# FlowKnow.net
KiCad netlist of a schematic drawn in EAGLE
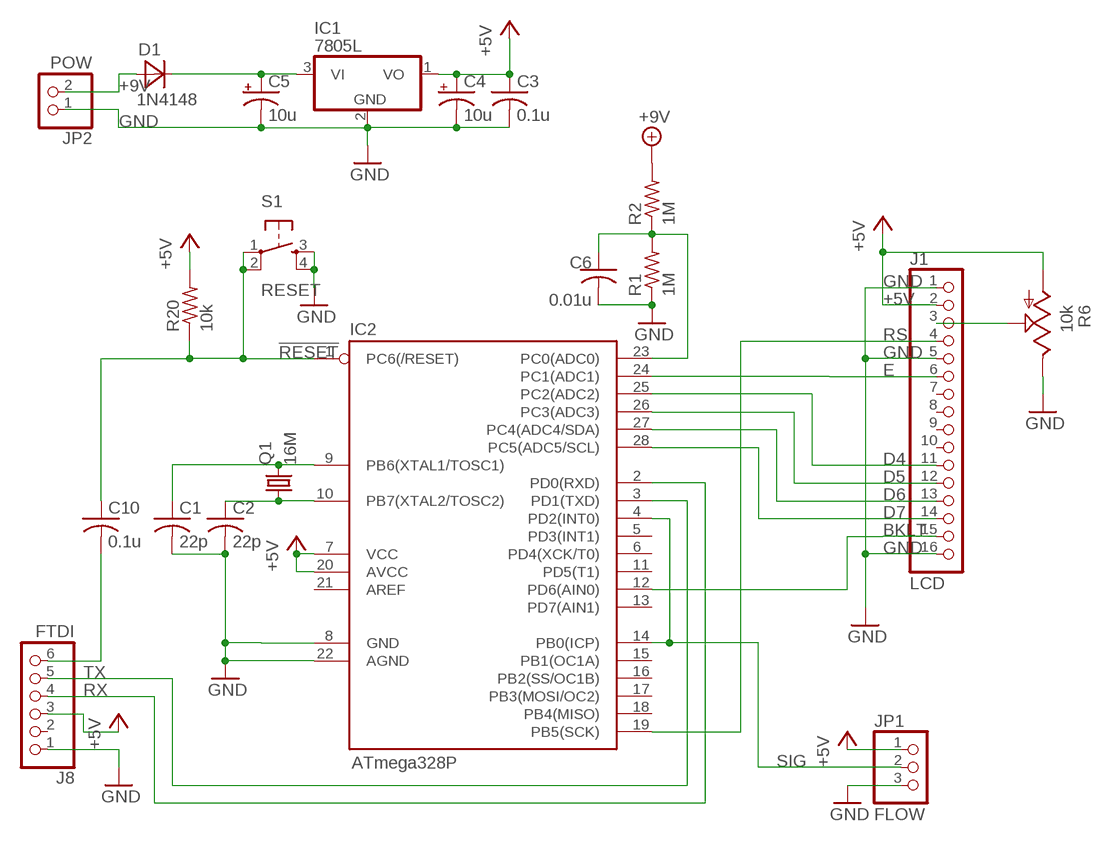
[diagram p0: schematic, sheet 1]

(export (version "E")
  (design (tool "Eeschema 10.0.6"))
  (components
    (comp (ref "C1")
      (value "22p")
      (footprint "eagle-import:C025-025X050")
      (libsource (lib "eagle-import") (part "C-US025-025X050"))
    )
    (comp (ref "C2")
      (value "22p")
      (footprint "eagle-import:C025-025X050")
      (libsource (lib "eagle-import") (part "C-US025-025X050"))
    )
    (comp (ref "C3")
      (value "0.1u")
      (footprint "eagle-import:C025-025X050")
      (libsource (lib "eagle-import") (part "C-US025-025X050"))
    )
    (comp (ref "C4")
      (value "10u")
      (footprint "eagle-import:E2-4")
      (libsource (lib "eagle-import") (part "CPOL-USE2-4"))
    )
    (comp (ref "C5")
      (value "10u")
      (footprint "eagle-import:E2,5-5")
      (libsource (lib "eagle-import") (part "CPOL-USE2.5-5"))
    )
    (comp (ref "C6")
      (value "0.01u")
      (footprint "eagle-import:C025-025X050")
      (libsource (lib "eagle-import") (part "C-US025-025X050"))
    )
    (comp (ref "C10")
      (value "0.1u")
      (footprint "eagle-import:C025-025X050")
      (libsource (lib "eagle-import") (part "C-US025-025X050"))
    )
    (comp (ref "D1")
      (value "1N4148")
      (footprint "eagle-import:DO35-5")
      (libsource (lib "eagle-import") (part "DIODE-DO35-5"))
    )
    (comp (ref "IC1")
      (value "7805L")
      (footprint "eagle-import:TO92")
      (libsource (lib "eagle-import") (part "78L05"))
    )
    (comp (ref "IC2")
      (value "ATmega328P")
      (footprint "eagle-import:DIL28-3")
      (libsource (lib "eagle-import") (part "AVR-MEGA8-PPTH"))
    )
    (comp (ref "J1")
      (value "LCD")
      (footprint "eagle-import:1X16")
      (libsource (lib "eagle-import") (part "PINHD-1X16"))
    )
    (comp (ref "J8")
      (value "FTDI")
      (footprint "eagle-import:1X06_90")
      (libsource (lib "eagle-import") (part "PINHD-1X6/90"))
    )
    (comp (ref "JP1")
      (value "FLOW")
      (footprint "eagle-import:1X03_90")
      (libsource (lib "eagle-import") (part "PINHD-1X3/90"))
    )
    (comp (ref "JP2")
      (value "POW")
      (footprint "eagle-import:1X02")
      (libsource (lib "eagle-import") (part "PINHD-1X2"))
    )
    (comp (ref "Q1")
      (value "16M")
      (footprint "eagle-import:HC49_S")
      (libsource (lib "eagle-import") (part "CRYSTALHC49S"))
    )
    (comp (ref "R1")
      (value "1M")
      (footprint "eagle-import:0204_7")
      (libsource (lib "eagle-import") (part "R-US_0204/7"))
    )
    (comp (ref "R2")
      (value "1M")
      (footprint "eagle-import:0204_7")
      (libsource (lib "eagle-import") (part "R-US_0204/7"))
    )
    (comp (ref "R6")
      (value "10k")
      (footprint "eagle-import:CT6")
      (libsource (lib "eagle-import") (part "TRIM_US-CT6"))
    )
    (comp (ref "R20")
      (value "10k")
      (footprint "eagle-import:0204_7")
      (libsource (lib "eagle-import") (part "R-US_0204/7"))
    )
    (comp (ref "S1")
      (value "RESET")
      (footprint "eagle-import:TACTILE-PTH")
      (libsource (lib "eagle-import") (part "TAC_SWITCHPTH"))
    )
  )
  (nets
    (net (code "1") (name "+5V") (class "Default")
      (node (ref "C3") (pin "1") (pinfunction "1_1") (pintype "passive"))
      (node (ref "C4") (pin "+") (pinfunction "+_+") (pintype "passive"))
      (node (ref "IC1") (pin "1") (pinfunction "VO_1") (pintype "passive"))
      (node (ref "IC2") (pin "20") (pinfunction "AVCC_20") (pintype "bidirectional"))
      (node (ref "IC2") (pin "7") (pinfunction "VCC_7") (pintype "bidirectional"))
      (node (ref "J1") (pin "2") (pinfunction "2_2") (pintype "passive"))
      (node (ref "J8") (pin "3") (pinfunction "3_3") (pintype "passive"))
      (node (ref "JP1") (pin "1") (pinfunction "1_1") (pintype "passive"))
      (node (ref "R20") (pin "2") (pinfunction "2_2") (pintype "passive"))
      (node (ref "R6") (pin "A") (pinfunction "A_A") (pintype "passive"))
    )
    (net (code "2") (name "+9V") (class "Default")
      (node (ref "D1") (pin "A") (pinfunction "A_A") (pintype "passive"))
      (node (ref "JP2") (pin "2") (pinfunction "2_2") (pintype "passive"))
      (node (ref "R2") (pin "2") (pinfunction "2_2") (pintype "passive"))
    )
    (net (code "3") (name "/BKLT") (class "Default")
      (node (ref "IC2") (pin "12") (pinfunction "PD6(AIN0)_12") (pintype "bidirectional"))
      (node (ref "J1") (pin "15") (pinfunction "15_15") (pintype "passive"))
    )
    (net (code "4") (name "/D4") (class "Default")
      (node (ref "IC2") (pin "25") (pinfunction "PC2(ADC2)_25") (pintype "bidirectional"))
      (node (ref "J1") (pin "11") (pinfunction "11_11") (pintype "passive"))
    )
    (net (code "5") (name "/D5") (class "Default")
      (node (ref "IC2") (pin "26") (pinfunction "PC3(ADC3)_26") (pintype "bidirectional"))
      (node (ref "J1") (pin "12") (pinfunction "12_12") (pintype "passive"))
    )
    (net (code "6") (name "/D6") (class "Default")
      (node (ref "IC2") (pin "27") (pinfunction "PC4(ADC4/SDA)_27") (pintype "bidirectional"))
      (node (ref "J1") (pin "13") (pinfunction "13_13") (pintype "passive"))
    )
    (net (code "7") (name "/D7") (class "Default")
      (node (ref "IC2") (pin "28") (pinfunction "PC5(ADC5/SCL)_28") (pintype "bidirectional"))
      (node (ref "J1") (pin "14") (pinfunction "14_14") (pintype "passive"))
    )
    (net (code "8") (name "/E") (class "Default")
      (node (ref "IC2") (pin "24") (pinfunction "PC1(ADC1)_24") (pintype "bidirectional"))
      (node (ref "J1") (pin "6") (pinfunction "6_6") (pintype "passive"))
    )
    (net (code "9") (name "/RS") (class "Default")
      (node (ref "IC2") (pin "19") (pinfunction "PB5(SCK)_19") (pintype "bidirectional"))
      (node (ref "J1") (pin "4") (pinfunction "4_4") (pintype "passive"))
    )
    (net (code "10") (name "/RX") (class "Default")
      (node (ref "IC2") (pin "2") (pinfunction "PD0(RXD)_2") (pintype "bidirectional"))
      (node (ref "J8") (pin "4") (pinfunction "4_4") (pintype "passive"))
    )
    (net (code "11") (name "/SIG") (class "Default")
      (node (ref "IC2") (pin "14") (pinfunction "PB0(ICP)_14") (pintype "bidirectional"))
      (node (ref "IC2") (pin "4") (pinfunction "PD2(INT0)_4") (pintype "bidirectional"))
      (node (ref "JP1") (pin "2") (pinfunction "2_2") (pintype "passive"))
    )
    (net (code "12") (name "/TX") (class "Default")
      (node (ref "IC2") (pin "3") (pinfunction "PD1(TXD)_3") (pintype "bidirectional"))
      (node (ref "J8") (pin "5") (pinfunction "5_5") (pintype "passive"))
    )
    (net (code "13") (name "/~{RESET}") (class "Default")
      (node (ref "C10") (pin "1") (pinfunction "1_1") (pintype "passive"))
      (node (ref "IC2") (pin "1") (pinfunction "PC6(/RESET)_1") (pintype "bidirectional"))
      (node (ref "R20") (pin "1") (pinfunction "1_1") (pintype "passive"))
      (node (ref "S1") (pin "1") (pinfunction "1_1") (pintype "passive"))
      (node (ref "S1") (pin "2") (pinfunction "2_2") (pintype "passive"))
    )
    (net (code "14") (name "GND") (class "Default")
      (node (ref "C1") (pin "2") (pinfunction "2_2") (pintype "passive"))
      (node (ref "C2") (pin "2") (pinfunction "2_2") (pintype "passive"))
      (node (ref "C3") (pin "2") (pinfunction "2_2") (pintype "passive"))
      (node (ref "C4") (pin "-") (pinfunction "-_-") (pintype "passive"))
      (node (ref "C5") (pin "-") (pinfunction "-_-") (pintype "passive"))
      (node (ref "C6") (pin "2") (pinfunction "2_2") (pintype "passive"))
      (node (ref "IC1") (pin "2") (pinfunction "GND_2") (pintype "passive"))
      (node (ref "IC2") (pin "22") (pinfunction "AGND_22") (pintype "bidirectional"))
      (node (ref "IC2") (pin "8") (pinfunction "GND_8") (pintype "bidirectional"))
      (node (ref "J1") (pin "1") (pinfunction "1_1") (pintype "passive"))
      (node (ref "J1") (pin "16") (pinfunction "16_16") (pintype "passive"))
      (node (ref "J1") (pin "5") (pinfunction "5_5") (pintype "passive"))
      (node (ref "J8") (pin "1") (pinfunction "1_1") (pintype "passive"))
      (node (ref "JP1") (pin "3") (pinfunction "3_3") (pintype "passive"))
      (node (ref "JP2") (pin "1") (pinfunction "1_1") (pintype "passive"))
      (node (ref "R1") (pin "1") (pinfunction "1_1") (pintype "passive"))
      (node (ref "R6") (pin "E") (pinfunction "E_E") (pintype "passive"))
      (node (ref "S1") (pin "3") (pinfunction "3_3") (pintype "passive"))
      (node (ref "S1") (pin "4") (pinfunction "4_4") (pintype "passive"))
    )
    (net (code "15") (name "Net-(C10-Pad2)") (class "Default")
      (node (ref "C10") (pin "2") (pinfunction "2_2") (pintype "passive"))
      (node (ref "J8") (pin "6") (pinfunction "6_6") (pintype "passive"))
    )
    (net (code "16") (name "Net-(IC1-VI)") (class "Default")
      (node (ref "C5") (pin "+") (pinfunction "+_+") (pintype "passive"))
      (node (ref "D1") (pin "C") (pinfunction "C_C") (pintype "passive"))
      (node (ref "IC1") (pin "3") (pinfunction "VI_3") (pintype "input"))
    )
    (net (code "17") (name "Net-(IC2-PB6(XTAL1{slash}TOSC1))") (class "Default")
      (node (ref "C1") (pin "1") (pinfunction "1_1") (pintype "passive"))
      (node (ref "IC2") (pin "9") (pinfunction "PB6(XTAL1/TOSC1)_9") (pintype "bidirectional"))
      (node (ref "Q1") (pin "2") (pinfunction "2_2") (pintype "passive"))
    )
    (net (code "18") (name "Net-(IC2-PB7(XTAL2{slash}TOSC2))") (class "Default")
      (node (ref "C2") (pin "1") (pinfunction "1_1") (pintype "passive"))
      (node (ref "IC2") (pin "10") (pinfunction "PB7(XTAL2/TOSC2)_10") (pintype "bidirectional"))
      (node (ref "Q1") (pin "1") (pinfunction "1_1") (pintype "passive"))
    )
    (net (code "19") (name "Net-(IC2-PC0(ADC0))") (class "Default")
      (node (ref "C6") (pin "1") (pinfunction "1_1") (pintype "passive"))
      (node (ref "IC2") (pin "23") (pinfunction "PC0(ADC0)_23") (pintype "bidirectional"))
      (node (ref "R1") (pin "2") (pinfunction "2_2") (pintype "passive"))
      (node (ref "R2") (pin "1") (pinfunction "1_1") (pintype "passive"))
    )
    (net (code "20") (name "Net-(J1-Pad3)") (class "Default")
      (node (ref "J1") (pin "3") (pinfunction "3_3") (pintype "passive"))
      (node (ref "R6") (pin "S") (pinfunction "S_S") (pintype "passive"))
    )
    (net (code "21") (name "unconnected-(IC2-AREF-Pad21)") (class "Default")
      (node (ref "IC2") (pin "21") (pinfunction "AREF_21") (pintype "bidirectional"))
    )
    (net (code "22") (name "unconnected-(IC2-PB1(OC1A)-Pad15)") (class "Default")
      (node (ref "IC2") (pin "15") (pinfunction "PB1(OC1A)_15") (pintype "bidirectional"))
    )
    (net (code "23") (name "unconnected-(IC2-PB2(SS{slash}OC1B)-Pad16)") (class "Default")
      (node (ref "IC2") (pin "16") (pinfunction "PB2(SS/OC1B)_16") (pintype "bidirectional"))
    )
    (net (code "24") (name "unconnected-(IC2-PB3(MOSI{slash}OC2)-Pad17)") (class "Default")
      (node (ref "IC2") (pin "17") (pinfunction "PB3(MOSI/OC2)_17") (pintype "bidirectional"))
    )
    (net (code "25") (name "unconnected-(IC2-PB4(MISO)-Pad18)") (class "Default")
      (node (ref "IC2") (pin "18") (pinfunction "PB4(MISO)_18") (pintype "bidirectional"))
    )
    (net (code "26") (name "unconnected-(IC2-PD3(INT1)-Pad5)") (class "Default")
      (node (ref "IC2") (pin "5") (pinfunction "PD3(INT1)_5") (pintype "bidirectional"))
    )
    (net (code "27") (name "unconnected-(IC2-PD4(XCK{slash}T0)-Pad6)") (class "Default")
      (node (ref "IC2") (pin "6") (pinfunction "PD4(XCK/T0)_6") (pintype "bidirectional"))
    )
    (net (code "28") (name "unconnected-(IC2-PD5(T1)-Pad11)") (class "Default")
      (node (ref "IC2") (pin "11") (pinfunction "PD5(T1)_11") (pintype "bidirectional"))
    )
    (net (code "29") (name "unconnected-(IC2-PD7(AIN1)-Pad13)") (class "Default")
      (node (ref "IC2") (pin "13") (pinfunction "PD7(AIN1)_13") (pintype "bidirectional"))
    )
    (net (code "30") (name "unconnected-(J1-Pad7)") (class "Default")
      (node (ref "J1") (pin "7") (pinfunction "7_7") (pintype "passive"))
    )
    (net (code "31") (name "unconnected-(J1-Pad8)") (class "Default")
      (node (ref "J1") (pin "8") (pinfunction "8_8") (pintype "passive"))
    )
    (net (code "32") (name "unconnected-(J1-Pad9)") (class "Default")
      (node (ref "J1") (pin "9") (pinfunction "9_9") (pintype "passive"))
    )
    (net (code "33") (name "unconnected-(J1-Pad10)") (class "Default")
      (node (ref "J1") (pin "10") (pinfunction "10_10") (pintype "passive"))
    )
    (net (code "34") (name "unconnected-(J8-Pad2)") (class "Default")
      (node (ref "J8") (pin "2") (pinfunction "2_2") (pintype "passive"))
    )
  )
)
